# Sheet1.net
KiCad netlist of a schematic drawn in Altium Designer
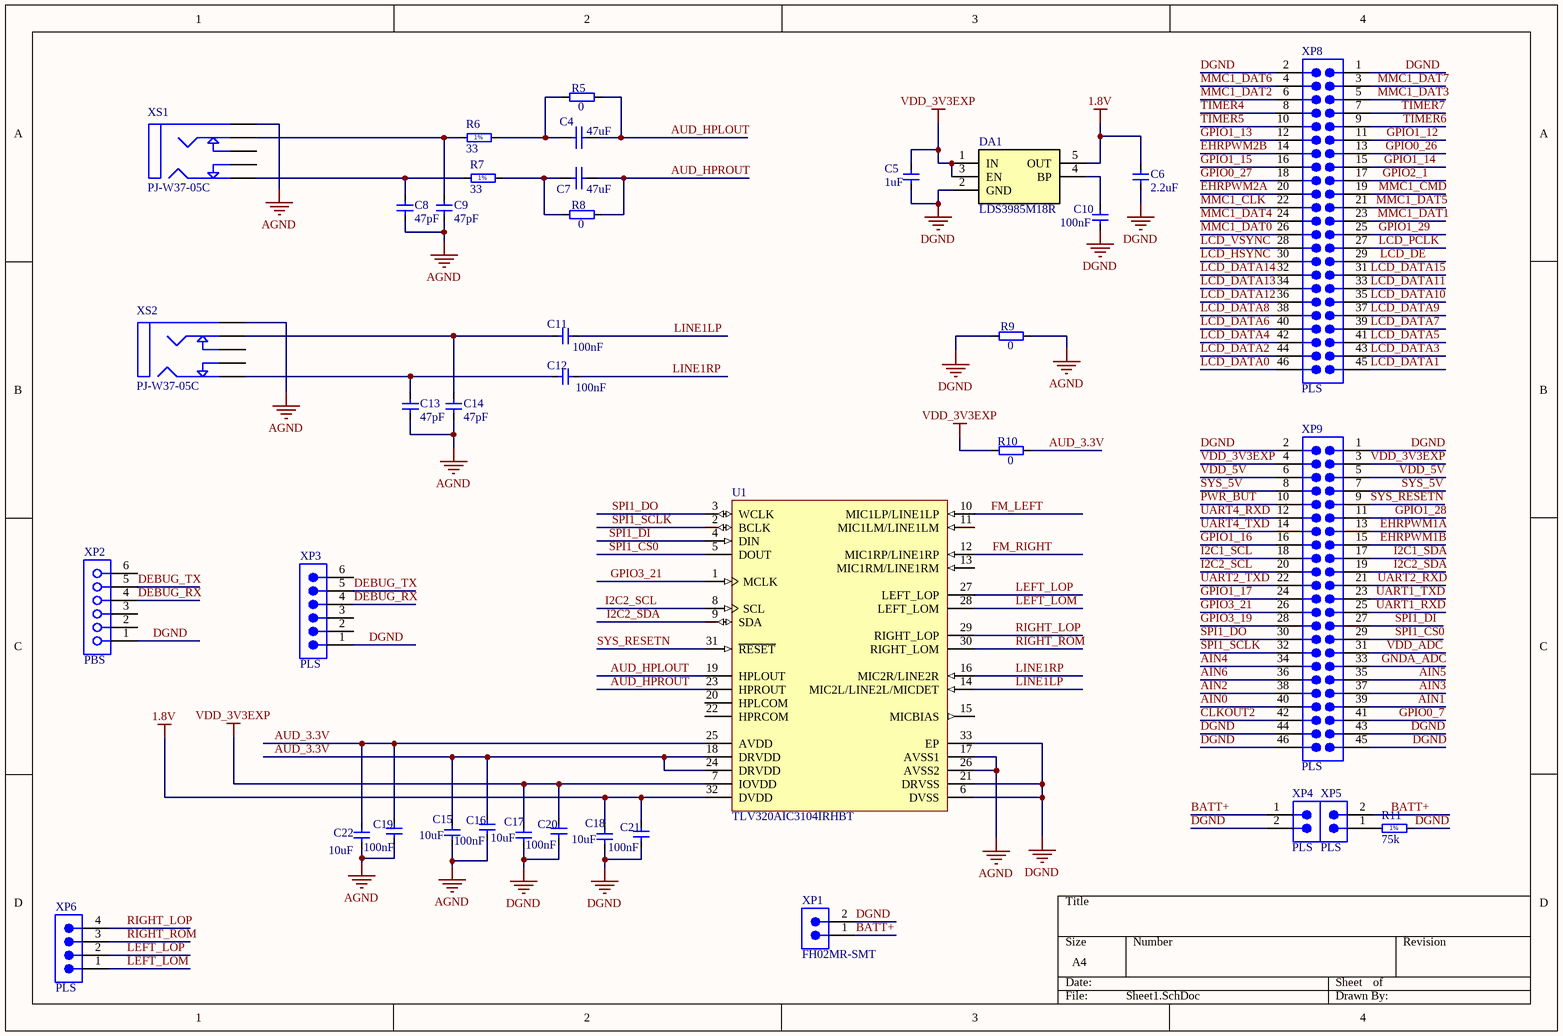
[diagram p0: Sheet1.SchDoc]

(export (version "E")
  (design (tool "Eeschema 10.0.6"))
  (components
    (comp (ref "C4")
      (value "47uF")
      (footprint "CAPC2012X140N")
      (description "Non-polarised capacitor")
      (fields
        (field (name "PART NUMBER") "CC0805_47UF_6.3V_20%_X5R")
        (field (name "VOLTAGE") "6.3V")
        (field (name "AUTHOR") "CERN DEM JLC")
      )
      (libsource (lib "Capacitors") (part "Capacitor - non polarized"))
    )
    (comp (ref "C5")
      (value "1uF")
      (footprint "CAP0603R")
      (description "SMD 0805 Capacitor")
      (fields
        (field (name "PART NUMBER") "CC0603_1UF_16V_10%_X7R")
        (field (name "VOLTAGE") "16V")
        (field (name "AUTHOR") "I. Kuznetsov")
      )
      (libsource (lib "Capacitor") (part "CAP_NON_POLAR"))
    )
    (comp (ref "C6")
      (value "2.2uF")
      (footprint "CAP0603R")
      (description "SMD 0805 Capacitor")
      (fields
        (field (name "PART NUMBER") "CC0603_2.2UF_6.3V_10%_X5R")
        (field (name "VOLTAGE") "6.3V")
        (field (name "AUTHOR") "I. Kuznetsov")
      )
      (libsource (lib "Capacitor") (part "CAP_NON_POLAR"))
    )
    (comp (ref "C7")
      (value "47uF")
      (footprint "CAPC2012X140N")
      (description "Non-polarised capacitor")
      (fields
        (field (name "PART NUMBER") "CC0805_47UF_6.3V_20%_X5R")
        (field (name "VOLTAGE") "6.3V")
        (field (name "AUTHOR") "CERN DEM JLC")
      )
      (libsource (lib "Capacitors") (part "Capacitor - non polarized"))
    )
    (comp (ref "C8")
      (value "47pF")
      (footprint "CAP0603R")
      (description "SMD 0805 Capacitor")
      (fields
        (field (name "PART NUMBER") "CC0603_47PF_50V_5%_NP0")
        (field (name "VOLTAGE") "50V")
        (field (name "AUTHOR") "I. Kuznetsov")
      )
      (libsource (lib "Capacitor") (part "CAP_NON_POLAR"))
    )
    (comp (ref "C9")
      (value "47pF")
      (footprint "CAP0603R")
      (description "SMD 0805 Capacitor")
      (fields
        (field (name "PART NUMBER") "CC0603_47PF_50V_5%_NP0")
        (field (name "VOLTAGE") "50V")
        (field (name "AUTHOR") "I. Kuznetsov")
      )
      (libsource (lib "Capacitor") (part "CAP_NON_POLAR"))
    )
    (comp (ref "C10")
      (value "100nF")
      (footprint "CAP0603R")
      (description "SMD 0805 Capacitor")
      (fields
        (field (name "PART NUMBER") "CC0603_100NF_50V_10%_X7R")
        (field (name "VOLTAGE") "50V")
        (field (name "AUTHOR") "I. Kuznetsov")
      )
      (libsource (lib "Capacitor") (part "CAP_NON_POLAR"))
    )
    (comp (ref "C11")
      (value "100nF")
      (footprint "CAP0603R")
      (description "SMD 0805 Capacitor")
      (fields
        (field (name "PART NUMBER") "CC0603_100NF_50V_10%_X7R")
        (field (name "VOLTAGE") "50V")
        (field (name "AUTHOR") "I. Kuznetsov")
      )
      (libsource (lib "Capacitor") (part "CAP_NON_POLAR"))
    )
    (comp (ref "C12")
      (value "100nF")
      (footprint "CAP0603R")
      (description "SMD 0805 Capacitor")
      (fields
        (field (name "PART NUMBER") "CC0603_100NF_50V_10%_X7R")
        (field (name "VOLTAGE") "50V")
        (field (name "AUTHOR") "I. Kuznetsov")
      )
      (libsource (lib "Capacitor") (part "CAP_NON_POLAR"))
    )
    (comp (ref "C13")
      (value "47pF")
      (footprint "CAP0603R")
      (description "SMD 0805 Capacitor")
      (fields
        (field (name "PART NUMBER") "CC0603_47PF_50V_5%_NP0")
        (field (name "VOLTAGE") "50V")
        (field (name "AUTHOR") "I. Kuznetsov")
      )
      (libsource (lib "Capacitor") (part "CAP_NON_POLAR"))
    )
    (comp (ref "C14")
      (value "47pF")
      (footprint "CAP0603R")
      (description "SMD 0805 Capacitor")
      (fields
        (field (name "PART NUMBER") "CC0603_47PF_50V_5%_NP0")
        (field (name "VOLTAGE") "50V")
        (field (name "AUTHOR") "I. Kuznetsov")
      )
      (libsource (lib "Capacitor") (part "CAP_NON_POLAR"))
    )
    (comp (ref "C15")
      (value "10uF")
      (footprint "CAP0603R")
      (description "SMD 0805 Capacitor")
      (fields
        (field (name "PART NUMBER") "CC0603_10UF_6.3V_20%_X5R")
        (field (name "VOLTAGE") "6.3V")
        (field (name "AUTHOR") "I. Kuznetsov")
      )
      (libsource (lib "Capacitor") (part "CAP_NON_POLAR"))
    )
    (comp (ref "C16")
      (value "100nF")
      (footprint "CAP0603R")
      (description "SMD 0805 Capacitor")
      (fields
        (field (name "PART NUMBER") "CC0603_100NF_50V_10%_X7R")
        (field (name "VOLTAGE") "50V")
        (field (name "AUTHOR") "I. Kuznetsov")
      )
      (libsource (lib "Capacitor") (part "CAP_NON_POLAR"))
    )
    (comp (ref "C17")
      (value "10uF")
      (footprint "CAP0603R")
      (description "SMD 0805 Capacitor")
      (fields
        (field (name "PART NUMBER") "CC0603_10UF_6.3V_20%_X5R")
        (field (name "VOLTAGE") "6.3V")
        (field (name "AUTHOR") "I. Kuznetsov")
      )
      (libsource (lib "Capacitor") (part "CAP_NON_POLAR"))
    )
    (comp (ref "C18")
      (value "10uF")
      (footprint "CAP0603R")
      (description "SMD 0805 Capacitor")
      (fields
        (field (name "PART NUMBER") "CC0603_10UF_6.3V_20%_X5R")
        (field (name "VOLTAGE") "6.3V")
        (field (name "AUTHOR") "I. Kuznetsov")
      )
      (libsource (lib "Capacitor") (part "CAP_NON_POLAR"))
    )
    (comp (ref "C19")
      (value "100nF")
      (footprint "CAP0603R")
      (description "SMD 0805 Capacitor")
      (fields
        (field (name "PART NUMBER") "CC0603_100NF_50V_10%_X7R")
        (field (name "VOLTAGE") "50V")
        (field (name "AUTHOR") "I. Kuznetsov")
      )
      (libsource (lib "Capacitor") (part "CAP_NON_POLAR"))
    )
    (comp (ref "C20")
      (value "100nF")
      (footprint "CAP0603R")
      (description "SMD 0805 Capacitor")
      (fields
        (field (name "PART NUMBER") "CC0603_100NF_50V_10%_X7R")
        (field (name "VOLTAGE") "50V")
        (field (name "AUTHOR") "I. Kuznetsov")
      )
      (libsource (lib "Capacitor") (part "CAP_NON_POLAR"))
    )
    (comp (ref "C21")
      (value "100nF")
      (footprint "CAP0603R")
      (description "SMD 0805 Capacitor")
      (fields
        (field (name "PART NUMBER") "CC0603_100NF_50V_10%_X7R")
        (field (name "VOLTAGE") "50V")
        (field (name "AUTHOR") "I. Kuznetsov")
      )
      (libsource (lib "Capacitor") (part "CAP_NON_POLAR"))
    )
    (comp (ref "C22")
      (value "10uF")
      (footprint "CAP0603R")
      (description "SMD 0805 Capacitor")
      (fields
        (field (name "PART NUMBER") "CC0603_10UF_6.3V_20%_X5R")
        (field (name "VOLTAGE") "6.3V")
        (field (name "AUTHOR") "I. Kuznetsov")
      )
      (libsource (lib "Capacitor") (part "CAP_NON_POLAR"))
    )
    (comp (ref "DA1")
      (value "LDS3985M18R")
      (footprint "SOT23-5")
      (fields (field (name "MANUFACTURER") "ST") (field (name "AUTHOR") "I. Kuznetsov"))
      (libsource (lib "IC And Semiconductor") (part "REG_5_PIN"))
    )
    (comp (ref "R5")
      (value "0")
      (footprint "RESC1608X55N")
      (description "Resistor")
      (fields
        (field (name "PART NUMBER") "R0603_0R_JUMPER")
        (field (name "MANUFACTURER") "GENERIC")
        (field (name "AUTHOR") "CERN DEM JLC")
      )
      (libsource (lib "Resistors") (part "Resistor"))
    )
    (comp (ref "R6")
      (value "33")
      (footprint "RES0603R")
      (fields
        (field (name "PART NUMBER") "R0603_33R_1%_0.1W_100PPM")
        (field (name "POWER") "0.1W")
        (field (name "TOLERANCE") "±1%")
        (field (name "AUTHOR") "CERN DEM JLC")
      )
      (libsource (lib "Resistor") (part "Resistor - 1%"))
    )
    (comp (ref "R7")
      (value "33")
      (footprint "RES0603R")
      (fields
        (field (name "PART NUMBER") "R0603_33R_1%_0.1W_100PPM")
        (field (name "POWER") "0.1W")
        (field (name "TOLERANCE") "±1%")
        (field (name "AUTHOR") "CERN DEM JLC")
      )
      (libsource (lib "Resistor") (part "Resistor - 1%"))
    )
    (comp (ref "R8")
      (value "0")
      (footprint "RESC1608X55N")
      (description "Resistor")
      (fields
        (field (name "PART NUMBER") "R0603_0R_JUMPER")
        (field (name "MANUFACTURER") "GENERIC")
        (field (name "AUTHOR") "CERN DEM JLC")
      )
      (libsource (lib "Resistors") (part "Resistor"))
    )
    (comp (ref "R9")
      (value "0")
      (footprint "RESC1608X55N")
      (description "Resistor")
      (fields
        (field (name "PART NUMBER") "R0603_0R_JUMPER")
        (field (name "MANUFACTURER") "GENERIC")
        (field (name "AUTHOR") "CERN DEM JLC")
      )
      (libsource (lib "Resistors") (part "Resistor"))
    )
    (comp (ref "R10")
      (value "0")
      (footprint "RESC1608X55N")
      (description "Resistor")
      (fields
        (field (name "PART NUMBER") "R0603_0R_JUMPER")
        (field (name "MANUFACTURER") "GENERIC")
        (field (name "AUTHOR") "CERN DEM JLC")
      )
      (libsource (lib "Resistors") (part "Resistor"))
    )
    (comp (ref "R11")
      (value "75k")
      (footprint "RES0603R")
      (fields
        (field (name "PART NUMBER") "R0603_75K_1%_0.1W_100PPM")
        (field (name "POWER") "0.1W")
        (field (name "TOLERANCE") "±1%")
        (field (name "AUTHOR") "CERN DEM JLC")
      )
      (libsource (lib "Resistor") (part "Resistor - 1%"))
    )
    (comp (ref "U1")
      (value "TLV320AIC3104IRHBT")
      (footprint "RHB32-3450X3450TP")
      (fields (field (name "MANUFACTURER") "Texas Instruments"))
      (libsource (lib "Altium Content Vault") (part "TI-TLV320AIC3104RHB32-3450X3450TP"))
    )
    (comp (ref "XP1") (value "FH02MR-SMT") (footprint "FH02MR-SMT") (libsource (lib "") (part "CN_02P_1W_1")))
    (comp (ref "XP2")
      (value "PBS")
      (footprint "PBS-06")
      (fields (field (name "PART NUMBER") "PBS-06"))
      (libsource (lib "Connector") (part "CN_06S_1W"))
    )
    (comp (ref "XP3")
      (value "PLS")
      (footprint "PLS-06")
      (fields (field (name "PART NUMBER") "PLS-06") (field (name "MANUFACTURER") "AUK"))
      (libsource (lib "Connector") (part "CN_06P_1W"))
    )
    (comp (ref "XP4")
      (value "PLS")
      (footprint "PLS-02")
      (fields (field (name "PART NUMBER") "PLS-02") (field (name "MANUFACTURER") "AUK"))
      (libsource (lib "Connector") (part "CN_02P_1W"))
    )
    (comp (ref "XP5")
      (value "PLS")
      (footprint "PLS-02")
      (fields (field (name "PART NUMBER") "PLS-02") (field (name "MANUFACTURER") "AUK"))
      (libsource (lib "") (part "CN_02P_1W_1"))
    )
    (comp (ref "XP6")
      (value "PLS")
      (footprint "PLS-04")
      (fields (field (name "PART NUMBER") "PLS-04") (field (name "MANUFACTURER") "AUK"))
      (libsource (lib "Connector") (part "CN_04P_1W"))
    )
    (comp (ref "XP8")
      (value "PLS")
      (footprint "PLD-46")
      (fields
        (field (name "PART NUMBER") "PLD-46")
        (field (name "MANUFACTURER") "AUK")
        (field (name "MANUFACTURER PART NUMBER") "PLS-16")
      )
      (libsource (lib "Connector") (part "CN_46P_2W"))
    )
    (comp (ref "XP9")
      (value "PLS")
      (footprint "PLD-46")
      (fields
        (field (name "PART NUMBER") "PLD-46")
        (field (name "MANUFACTURER") "AUK")
        (field (name "MANUFACTURER PART NUMBER") "PLS-16")
      )
      (libsource (lib "Connector") (part "CN_46P_2W"))
    )
    (comp (ref "XS1")
      (value "PJ-W37-05C")
      (footprint "PJ-W37-05C")
      (description "3.5 mm Jack Connector")
      (libsource (lib "Connector") (part "SOC_3.5_5_PIN"))
    )
    (comp (ref "XS2")
      (value "PJ-W37-05C")
      (footprint "PJ-W37-05C")
      (description "3.5 mm Jack Connector")
      (libsource (lib "Connector") (part "SOC_3.5_5_PIN"))
    )
  )
  (nets
    (net (code "1") (name "/AIN0") (class "Default")
      (node (ref "XP9") (pin "40") (pinfunction "40_40") (pintype "passive"))
    )
    (net (code "2") (name "/AIN1") (class "Default")
      (node (ref "XP9") (pin "39") (pinfunction "39_39") (pintype "passive"))
    )
    (net (code "3") (name "/AIN2") (class "Default")
      (node (ref "XP9") (pin "38") (pinfunction "38_38") (pintype "passive"))
    )
    (net (code "4") (name "/AIN3") (class "Default")
      (node (ref "XP9") (pin "37") (pinfunction "37_37") (pintype "passive"))
    )
    (net (code "5") (name "/AIN4") (class "Default")
      (node (ref "XP9") (pin "34") (pinfunction "34_34") (pintype "passive"))
    )
    (net (code "6") (name "/AIN5") (class "Default")
      (node (ref "XP9") (pin "35") (pinfunction "35_35") (pintype "passive"))
    )
    (net (code "7") (name "/AIN6") (class "Default")
      (node (ref "XP9") (pin "36") (pinfunction "36_36") (pintype "passive"))
    )
    (net (code "8") (name "/AUD_3.3V") (class "Default")
      (node (ref "C15") (pin "2") (pinfunction "2_2") (pintype "passive"))
      (node (ref "C16") (pin "1") (pinfunction "1_1") (pintype "passive"))
      (node (ref "C19") (pin "1") (pinfunction "1_1") (pintype "passive"))
      (node (ref "C22") (pin "2") (pinfunction "2_2") (pintype "passive"))
      (node (ref "R10") (pin "2") (pinfunction "2_2") (pintype "passive"))
      (node (ref "U1") (pin "18") (pinfunction "DRVDD_18") (pintype "power_in"))
      (node (ref "U1") (pin "24") (pinfunction "DRVDD_24") (pintype "power_in"))
      (node (ref "U1") (pin "25") (pinfunction "AVDD_25") (pintype "power_in"))
    )
    (net (code "9") (name "/AUD_HPLOUT") (class "Default")
      (node (ref "C4") (pin "2") (pinfunction "2_2") (pintype "passive"))
      (node (ref "R5") (pin "2") (pinfunction "2_2") (pintype "passive"))
      (node (ref "U1") (pin "19") (pinfunction "HPLOUT_19") (pintype "tri_state"))
    )
    (net (code "10") (name "/AUD_HPROUT") (class "Default")
      (node (ref "C7") (pin "2") (pinfunction "2_2") (pintype "passive"))
      (node (ref "R8") (pin "2") (pinfunction "2_2") (pintype "passive"))
      (node (ref "U1") (pin "23") (pinfunction "HPROUT_23") (pintype "tri_state"))
    )
    (net (code "11") (name "/BATT+") (class "Default")
      (node (ref "XP1") (pin "1") (pinfunction "1_1") (pintype "passive"))
      (node (ref "XP4") (pin "1") (pinfunction "1_1") (pintype "passive"))
      (node (ref "XP5") (pin "2") (pinfunction "2_2") (pintype "passive"))
    )
    (net (code "12") (name "/CLKOUT2") (class "Default")
      (node (ref "XP9") (pin "42") (pinfunction "42_42") (pintype "passive"))
    )
    (net (code "13") (name "/DEBUG_RX") (class "Default")
      (node (ref "XP2") (pin "4") (pinfunction "4_4") (pintype "passive"))
      (node (ref "XP3") (pin "4") (pinfunction "4_4") (pintype "passive"))
    )
    (net (code "14") (name "/DEBUG_TX") (class "Default")
      (node (ref "XP2") (pin "5") (pinfunction "5_5") (pintype "passive"))
      (node (ref "XP3") (pin "5") (pinfunction "5_5") (pintype "passive"))
    )
    (net (code "15") (name "/EHRPWM1A") (class "Default")
      (node (ref "XP9") (pin "13") (pinfunction "13_13") (pintype "passive"))
    )
    (net (code "16") (name "/EHRPWM1B") (class "Default")
      (node (ref "XP9") (pin "15") (pinfunction "15_15") (pintype "passive"))
    )
    (net (code "17") (name "/EHRPWM2A") (class "Default")
      (node (ref "XP8") (pin "20") (pinfunction "20_20") (pintype "passive"))
    )
    (net (code "18") (name "/EHRPWM2B") (class "Default")
      (node (ref "XP8") (pin "14") (pinfunction "14_14") (pintype "passive"))
    )
    (net (code "19") (name "/FM_LEFT") (class "Default")
      (node (ref "U1") (pin "10") (pinfunction "MIC1LP/LINE1LP_10") (pintype "input"))
    )
    (net (code "20") (name "/FM_RIGHT") (class "Default")
      (node (ref "U1") (pin "12") (pinfunction "MIC1RP/LINE1RP_12") (pintype "input"))
    )
    (net (code "21") (name "/GNDA_ADC") (class "Default")
      (node (ref "XP9") (pin "33") (pinfunction "33_33") (pintype "passive"))
    )
    (net (code "22") (name "/GPIO0_7") (class "Default")
      (node (ref "XP9") (pin "41") (pinfunction "41_41") (pintype "passive"))
    )
    (net (code "23") (name "/GPIO0_26") (class "Default")
      (node (ref "XP8") (pin "13") (pinfunction "13_13") (pintype "passive"))
    )
    (net (code "24") (name "/GPIO0_27") (class "Default")
      (node (ref "XP8") (pin "18") (pinfunction "18_18") (pintype "passive"))
    )
    (net (code "25") (name "/GPIO1_12") (class "Default")
      (node (ref "XP8") (pin "11") (pinfunction "11_11") (pintype "passive"))
    )
    (net (code "26") (name "/GPIO1_13") (class "Default")
      (node (ref "XP8") (pin "12") (pinfunction "12_12") (pintype "passive"))
    )
    (net (code "27") (name "/GPIO1_14") (class "Default")
      (node (ref "XP8") (pin "15") (pinfunction "15_15") (pintype "passive"))
    )
    (net (code "28") (name "/GPIO1_15") (class "Default")
      (node (ref "XP8") (pin "16") (pinfunction "16_16") (pintype "passive"))
    )
    (net (code "29") (name "/GPIO1_16") (class "Default")
      (node (ref "XP9") (pin "16") (pinfunction "16_16") (pintype "passive"))
    )
    (net (code "30") (name "/GPIO1_17") (class "Default")
      (node (ref "XP9") (pin "24") (pinfunction "24_24") (pintype "passive"))
    )
    (net (code "31") (name "/GPIO1_28") (class "Default")
      (node (ref "XP9") (pin "11") (pinfunction "11_11") (pintype "passive"))
    )
    (net (code "32") (name "/GPIO1_29") (class "Default")
      (node (ref "XP8") (pin "25") (pinfunction "25_25") (pintype "passive"))
    )
    (net (code "33") (name "/GPIO2_1") (class "Default")
      (node (ref "XP8") (pin "17") (pinfunction "17_17") (pintype "passive"))
    )
    (net (code "34") (name "/GPIO3_19") (class "Default")
      (node (ref "XP9") (pin "28") (pinfunction "28_28") (pintype "passive"))
    )
    (net (code "35") (name "/GPIO3_21") (class "Default")
      (node (ref "U1") (pin "1") (pinfunction "MCLK_1") (pintype "input"))
      (node (ref "XP9") (pin "26") (pinfunction "26_26") (pintype "passive"))
    )
    (net (code "36") (name "/I2C1_SCL") (class "Default")
      (node (ref "XP9") (pin "18") (pinfunction "18_18") (pintype "passive"))
    )
    (net (code "37") (name "/I2C1_SDA") (class "Default")
      (node (ref "XP9") (pin "17") (pinfunction "17_17") (pintype "passive"))
    )
    (net (code "38") (name "/I2C2_SCL") (class "Default")
      (node (ref "U1") (pin "8") (pinfunction "SCL_8") (pintype "input"))
      (node (ref "XP9") (pin "20") (pinfunction "20_20") (pintype "passive"))
    )
    (net (code "39") (name "/I2C2_SDA") (class "Default")
      (node (ref "U1") (pin "9") (pinfunction "SDA_9") (pintype "bidirectional"))
      (node (ref "XP9") (pin "19") (pinfunction "19_19") (pintype "passive"))
    )
    (net (code "40") (name "/LCD_DATA0") (class "Default")
      (node (ref "XP8") (pin "46") (pinfunction "46_46") (pintype "passive"))
    )
    (net (code "41") (name "/LCD_DATA1") (class "Default")
      (node (ref "XP8") (pin "45") (pinfunction "45_45") (pintype "passive"))
    )
    (net (code "42") (name "/LCD_DATA2") (class "Default")
      (node (ref "XP8") (pin "44") (pinfunction "44_44") (pintype "passive"))
    )
    (net (code "43") (name "/LCD_DATA3") (class "Default")
      (node (ref "XP8") (pin "43") (pinfunction "43_43") (pintype "passive"))
    )
    (net (code "44") (name "/LCD_DATA4") (class "Default")
      (node (ref "XP8") (pin "42") (pinfunction "42_42") (pintype "passive"))
    )
    (net (code "45") (name "/LCD_DATA5") (class "Default")
      (node (ref "XP8") (pin "41") (pinfunction "41_41") (pintype "passive"))
    )
    (net (code "46") (name "/LCD_DATA6") (class "Default")
      (node (ref "XP8") (pin "40") (pinfunction "40_40") (pintype "passive"))
    )
    (net (code "47") (name "/LCD_DATA7") (class "Default")
      (node (ref "XP8") (pin "39") (pinfunction "39_39") (pintype "passive"))
    )
    (net (code "48") (name "/LCD_DATA8") (class "Default")
      (node (ref "XP8") (pin "38") (pinfunction "38_38") (pintype "passive"))
    )
    (net (code "49") (name "/LCD_DATA9") (class "Default")
      (node (ref "XP8") (pin "37") (pinfunction "37_37") (pintype "passive"))
    )
    (net (code "50") (name "/LCD_DATA10") (class "Default")
      (node (ref "XP8") (pin "35") (pinfunction "35_35") (pintype "passive"))
    )
    (net (code "51") (name "/LCD_DATA11") (class "Default")
      (node (ref "XP8") (pin "33") (pinfunction "33_33") (pintype "passive"))
    )
    (net (code "52") (name "/LCD_DATA12") (class "Default")
      (node (ref "XP8") (pin "36") (pinfunction "36_36") (pintype "passive"))
    )
    (net (code "53") (name "/LCD_DATA13") (class "Default")
      (node (ref "XP8") (pin "34") (pinfunction "34_34") (pintype "passive"))
    )
    (net (code "54") (name "/LCD_DATA14") (class "Default")
      (node (ref "XP8") (pin "32") (pinfunction "32_32") (pintype "passive"))
    )
    (net (code "55") (name "/LCD_DATA15") (class "Default")
      (node (ref "XP8") (pin "31") (pinfunction "31_31") (pintype "passive"))
    )
    (net (code "56") (name "/LCD_DE") (class "Default")
      (node (ref "XP8") (pin "29") (pinfunction "29_29") (pintype "passive"))
    )
    (net (code "57") (name "/LCD_HSYNC") (class "Default")
      (node (ref "XP8") (pin "30") (pinfunction "30_30") (pintype "passive"))
    )
    (net (code "58") (name "/LCD_PCLK") (class "Default")
      (node (ref "XP8") (pin "27") (pinfunction "27_27") (pintype "passive"))
    )
    (net (code "59") (name "/LCD_VSYNC") (class "Default")
      (node (ref "XP8") (pin "28") (pinfunction "28_28") (pintype "passive"))
    )
    (net (code "60") (name "/LEFT_LOM") (class "Default")
      (node (ref "U1") (pin "28") (pinfunction "LEFT_LOM_28") (pintype "tri_state"))
      (node (ref "XP6") (pin "1") (pinfunction "1_1") (pintype "passive"))
    )
    (net (code "61") (name "/LEFT_LOP") (class "Default")
      (node (ref "U1") (pin "27") (pinfunction "LEFT_LOP_27") (pintype "tri_state"))
      (node (ref "XP6") (pin "2") (pinfunction "2_2") (pintype "passive"))
    )
    (net (code "62") (name "/LINE1LP") (class "Default")
      (node (ref "C11") (pin "2") (pinfunction "2_2") (pintype "passive"))
      (node (ref "U1") (pin "14") (pinfunction "MIC2L/LINE2L/MICDET_14") (pintype "input"))
    )
    (net (code "63") (name "/LINE1RP") (class "Default")
      (node (ref "C12") (pin "2") (pinfunction "2_2") (pintype "passive"))
      (node (ref "U1") (pin "16") (pinfunction "MIC2R/LINE2R_16") (pintype "input"))
    )
    (net (code "64") (name "/MMC1_CLK") (class "Default")
      (node (ref "XP8") (pin "22") (pinfunction "22_22") (pintype "passive"))
    )
    (net (code "65") (name "/MMC1_CMD") (class "Default")
      (node (ref "XP8") (pin "19") (pinfunction "19_19") (pintype "passive"))
    )
    (net (code "66") (name "/MMC1_DAT0") (class "Default")
      (node (ref "XP8") (pin "26") (pinfunction "26_26") (pintype "passive"))
    )
    (net (code "67") (name "/MMC1_DAT1") (class "Default")
      (node (ref "XP8") (pin "23") (pinfunction "23_23") (pintype "passive"))
    )
    (net (code "68") (name "/MMC1_DAT2") (class "Default")
      (node (ref "XP8") (pin "6") (pinfunction "6_6") (pintype "passive"))
    )
    (net (code "69") (name "/MMC1_DAT3") (class "Default")
      (node (ref "XP8") (pin "5") (pinfunction "5_5") (pintype "passive"))
    )
    (net (code "70") (name "/MMC1_DAT4") (class "Default")
      (node (ref "XP8") (pin "24") (pinfunction "24_24") (pintype "passive"))
    )
    (net (code "71") (name "/MMC1_DAT5") (class "Default")
      (node (ref "XP8") (pin "21") (pinfunction "21_21") (pintype "passive"))
    )
    (net (code "72") (name "/MMC1_DAT6") (class "Default")
      (node (ref "XP8") (pin "4") (pinfunction "4_4") (pintype "passive"))
    )
    (net (code "73") (name "/MMC1_DAT7") (class "Default")
      (node (ref "XP8") (pin "3") (pinfunction "3_3") (pintype "passive"))
    )
    (net (code "74") (name "/PWR_BUT") (class "Default")
      (node (ref "XP9") (pin "10") (pinfunction "10_10") (pintype "passive"))
    )
    (net (code "75") (name "/RIGHT_LOP") (class "Default")
      (node (ref "U1") (pin "29") (pinfunction "RIGHT_LOP_29") (pintype "tri_state"))
      (node (ref "XP6") (pin "4") (pinfunction "4_4") (pintype "passive"))
    )
    (net (code "76") (name "/RIGHT_ROM") (class "Default")
      (node (ref "U1") (pin "30") (pinfunction "RIGHT_LOM_30") (pintype "tri_state"))
      (node (ref "XP6") (pin "3") (pinfunction "3_3") (pintype "passive"))
    )
    (net (code "77") (name "/SPI1_CS0") (class "Default")
      (node (ref "U1") (pin "5") (pinfunction "DOUT_5") (pintype "tri_state"))
      (node (ref "XP9") (pin "29") (pinfunction "29_29") (pintype "passive"))
    )
    (net (code "78") (name "/SPI1_DI") (class "Default")
      (node (ref "U1") (pin "4") (pinfunction "DIN_4") (pintype "input"))
      (node (ref "XP9") (pin "27") (pinfunction "27_27") (pintype "passive"))
    )
    (net (code "79") (name "/SPI1_DO") (class "Default")
      (node (ref "U1") (pin "3") (pinfunction "WCLK_3") (pintype "bidirectional"))
      (node (ref "XP9") (pin "30") (pinfunction "30_30") (pintype "passive"))
    )
    (net (code "80") (name "/SPI1_SCLK") (class "Default")
      (node (ref "U1") (pin "2") (pinfunction "BCLK_2") (pintype "bidirectional"))
      (node (ref "XP9") (pin "32") (pinfunction "32_32") (pintype "passive"))
    )
    (net (code "81") (name "/SYS_5V") (class "Default")
      (node (ref "XP9") (pin "7") (pinfunction "7_7") (pintype "passive"))
      (node (ref "XP9") (pin "8") (pinfunction "8_8") (pintype "passive"))
    )
    (net (code "82") (name "/SYS_RESETN") (class "Default")
      (node (ref "U1") (pin "31") (pinfunction "~{RESET}_31") (pintype "input"))
      (node (ref "XP9") (pin "9") (pinfunction "9_9") (pintype "passive"))
    )
    (net (code "83") (name "/TIMER4") (class "Default")
      (node (ref "XP8") (pin "8") (pinfunction "8_8") (pintype "passive"))
    )
    (net (code "84") (name "/TIMER5") (class "Default")
      (node (ref "XP8") (pin "10") (pinfunction "10_10") (pintype "passive"))
    )
    (net (code "85") (name "/TIMER6") (class "Default")
      (node (ref "XP8") (pin "9") (pinfunction "9_9") (pintype "passive"))
    )
    (net (code "86") (name "/TIMER7") (class "Default")
      (node (ref "XP8") (pin "7") (pinfunction "7_7") (pintype "passive"))
    )
    (net (code "87") (name "/UART1_RXD") (class "Default")
      (node (ref "XP9") (pin "25") (pinfunction "25_25") (pintype "passive"))
    )
    (net (code "88") (name "/UART1_TXD") (class "Default")
      (node (ref "XP9") (pin "23") (pinfunction "23_23") (pintype "passive"))
    )
    (net (code "89") (name "/UART2_RXD") (class "Default")
      (node (ref "XP9") (pin "21") (pinfunction "21_21") (pintype "passive"))
    )
    (net (code "90") (name "/UART2_TXD") (class "Default")
      (node (ref "XP9") (pin "22") (pinfunction "22_22") (pintype "passive"))
    )
    (net (code "91") (name "/UART4_RXD") (class "Default")
      (node (ref "XP9") (pin "12") (pinfunction "12_12") (pintype "passive"))
    )
    (net (code "92") (name "/UART4_TXD") (class "Default")
      (node (ref "XP9") (pin "14") (pinfunction "14_14") (pintype "passive"))
    )
    (net (code "93") (name "/VDD_5V") (class "Default")
      (node (ref "XP9") (pin "5") (pinfunction "5_5") (pintype "passive"))
      (node (ref "XP9") (pin "6") (pinfunction "6_6") (pintype "passive"))
    )
    (net (code "94") (name "/VDD_ADC") (class "Default")
      (node (ref "XP9") (pin "31") (pinfunction "31_31") (pintype "passive"))
    )
    (net (code "95") (name "1.8V") (class "Default")
      (node (ref "C18") (pin "2") (pinfunction "2_2") (pintype "passive"))
      (node (ref "C21") (pin "1") (pinfunction "1_1") (pintype "passive"))
      (node (ref "C6") (pin "2") (pinfunction "2_2") (pintype "passive"))
      (node (ref "DA1") (pin "5") (pinfunction "OUT_5") (pintype "passive"))
      (node (ref "U1") (pin "32") (pinfunction "DVDD_32") (pintype "power_in"))
    )
    (net (code "96") (name "AGND") (class "Default")
      (node (ref "C13") (pin "2") (pinfunction "2_2") (pintype "passive"))
      (node (ref "C14") (pin "2") (pinfunction "2_2") (pintype "passive"))
      (node (ref "C15") (pin "1") (pinfunction "1_1") (pintype "passive"))
      (node (ref "C16") (pin "2") (pinfunction "2_2") (pintype "passive"))
      (node (ref "C19") (pin "2") (pinfunction "2_2") (pintype "passive"))
      (node (ref "C22") (pin "1") (pinfunction "1_1") (pintype "passive"))
      (node (ref "C8") (pin "2") (pinfunction "2_2") (pintype "passive"))
      (node (ref "C9") (pin "2") (pinfunction "2_2") (pintype "passive"))
      (node (ref "R9") (pin "2") (pinfunction "2_2") (pintype "passive"))
      (node (ref "U1") (pin "17") (pinfunction "AVSS1_17") (pintype "power_in"))
      (node (ref "U1") (pin "26") (pinfunction "AVSS2_26") (pintype "power_in"))
      (node (ref "XS1") (pin "1") (pinfunction "1_1") (pintype "passive"))
      (node (ref "XS2") (pin "1") (pinfunction "1_1") (pintype "passive"))
    )
    (net (code "97") (name "DGND") (class "Default")
      (node (ref "C10") (pin "1") (pinfunction "1_1") (pintype "passive"))
      (node (ref "C17") (pin "1") (pinfunction "1_1") (pintype "passive"))
      (node (ref "C18") (pin "1") (pinfunction "1_1") (pintype "passive"))
      (node (ref "C20") (pin "2") (pinfunction "2_2") (pintype "passive"))
      (node (ref "C21") (pin "2") (pinfunction "2_2") (pintype "passive"))
      (node (ref "C5") (pin "2") (pinfunction "2_2") (pintype "passive"))
      (node (ref "C6") (pin "1") (pinfunction "1_1") (pintype "passive"))
      (node (ref "DA1") (pin "2") (pinfunction "GND_2") (pintype "passive"))
      (node (ref "R11") (pin "2") (pinfunction "2_2") (pintype "passive"))
      (node (ref "R9") (pin "1") (pinfunction "1_1") (pintype "passive"))
      (node (ref "U1") (pin "21") (pinfunction "DRVSS_21") (pintype "power_in"))
      (node (ref "U1") (pin "33") (pinfunction "EP_33") (pintype "power_in"))
      (node (ref "U1") (pin "6") (pinfunction "DVSS_6") (pintype "power_in"))
      (node (ref "XP1") (pin "2") (pinfunction "2_2") (pintype "passive"))
      (node (ref "XP2") (pin "1") (pinfunction "1_1") (pintype "passive"))
      (node (ref "XP3") (pin "1") (pinfunction "1_1") (pintype "passive"))
      (node (ref "XP4") (pin "2") (pinfunction "2_2") (pintype "passive"))
      (node (ref "XP8") (pin "1") (pinfunction "1_1") (pintype "passive"))
      (node (ref "XP8") (pin "2") (pinfunction "2_2") (pintype "passive"))
      (node (ref "XP9") (pin "1") (pinfunction "1_1") (pintype "passive"))
      (node (ref "XP9") (pin "2") (pinfunction "2_2") (pintype "passive"))
      (node (ref "XP9") (pin "43") (pinfunction "43_43") (pintype "passive"))
      (node (ref "XP9") (pin "44") (pinfunction "44_44") (pintype "passive"))
      (node (ref "XP9") (pin "45") (pinfunction "45_45") (pintype "passive"))
      (node (ref "XP9") (pin "46") (pinfunction "46_46") (pintype "passive"))
    )
    (net (code "98") (name "Net-(C4-Pad1)") (class "Default")
      (node (ref "C4") (pin "1") (pinfunction "1_1") (pintype "passive"))
      (node (ref "R5") (pin "1") (pinfunction "1_1") (pintype "passive"))
      (node (ref "R6") (pin "2") (pinfunction "2_2") (pintype "passive"))
    )
    (net (code "99") (name "Net-(C7-Pad1)") (class "Default")
      (node (ref "C7") (pin "1") (pinfunction "1_1") (pintype "passive"))
      (node (ref "R7") (pin "2") (pinfunction "2_2") (pintype "passive"))
      (node (ref "R8") (pin "1") (pinfunction "1_1") (pintype "passive"))
    )
    (net (code "100") (name "Net-(C8-Pad1)") (class "Default")
      (node (ref "C8") (pin "1") (pinfunction "1_1") (pintype "passive"))
      (node (ref "R7") (pin "1") (pinfunction "1_1") (pintype "passive"))
      (node (ref "XS1") (pin "3") (pinfunction "3_3") (pintype "passive"))
    )
    (net (code "101") (name "Net-(C9-Pad1)") (class "Default")
      (node (ref "C9") (pin "1") (pinfunction "1_1") (pintype "passive"))
      (node (ref "R6") (pin "1") (pinfunction "1_1") (pintype "passive"))
      (node (ref "XS1") (pin "2") (pinfunction "2_2") (pintype "passive"))
    )
    (net (code "102") (name "Net-(C11-Pad1)") (class "Default")
      (node (ref "C11") (pin "1") (pinfunction "1_1") (pintype "passive"))
      (node (ref "C14") (pin "1") (pinfunction "1_1") (pintype "passive"))
      (node (ref "XS2") (pin "2") (pinfunction "2_2") (pintype "passive"))
    )
    (net (code "103") (name "Net-(C12-Pad1)") (class "Default")
      (node (ref "C12") (pin "1") (pinfunction "1_1") (pintype "passive"))
      (node (ref "C13") (pin "1") (pinfunction "1_1") (pintype "passive"))
      (node (ref "XS2") (pin "3") (pinfunction "3_3") (pintype "passive"))
    )
    (net (code "104") (name "Net-(DA1-BP)") (class "Default")
      (node (ref "C10") (pin "2") (pinfunction "2_2") (pintype "passive"))
      (node (ref "DA1") (pin "4") (pinfunction "BP_4") (pintype "passive"))
    )
    (net (code "105") (name "Net-(R11-Pad1)") (class "Default")
      (node (ref "R11") (pin "1") (pinfunction "1_1") (pintype "passive"))
      (node (ref "XP5") (pin "1") (pinfunction "1_1") (pintype "passive"))
    )
    (net (code "106") (name "VDD_3V3EXP") (class "Default")
      (node (ref "C17") (pin "2") (pinfunction "2_2") (pintype "passive"))
      (node (ref "C20") (pin "1") (pinfunction "1_1") (pintype "passive"))
      (node (ref "C5") (pin "1") (pinfunction "1_1") (pintype "passive"))
      (node (ref "DA1") (pin "1") (pinfunction "IN_1") (pintype "passive"))
      (node (ref "DA1") (pin "3") (pinfunction "EN_3") (pintype "passive"))
      (node (ref "R10") (pin "1") (pinfunction "1_1") (pintype "passive"))
      (node (ref "U1") (pin "7") (pinfunction "IOVDD_7") (pintype "power_in"))
      (node (ref "XP9") (pin "3") (pinfunction "3_3") (pintype "passive"))
      (node (ref "XP9") (pin "4") (pinfunction "4_4") (pintype "passive"))
    )
    (net (code "107") (name "unconnected-(U1-HPLCOM-Pad20)") (class "Default")
      (node (ref "U1") (pin "20") (pinfunction "HPLCOM_20") (pintype "tri_state"))
    )
    (net (code "108") (name "unconnected-(U1-HPRCOM-Pad22)") (class "Default")
      (node (ref "U1") (pin "22") (pinfunction "HPRCOM_22") (pintype "tri_state"))
    )
    (net (code "109") (name "unconnected-(U1-MIC1LM{slash}LINE1LM-Pad11)") (class "Default")
      (node (ref "U1") (pin "11") (pinfunction "MIC1LM/LINE1LM_11") (pintype "input"))
    )
    (net (code "110") (name "unconnected-(U1-MIC1RM{slash}LINE1RM-Pad13)") (class "Default")
      (node (ref "U1") (pin "13") (pinfunction "MIC1RM/LINE1RM_13") (pintype "input"))
    )
    (net (code "111") (name "unconnected-(U1-MICBIAS-Pad15)") (class "Default")
      (node (ref "U1") (pin "15") (pinfunction "MICBIAS_15") (pintype "output"))
    )
    (net (code "112") (name "unconnected-(XP2-Pad2)") (class "Default")
      (node (ref "XP2") (pin "2") (pinfunction "2_2") (pintype "passive"))
    )
    (net (code "113") (name "unconnected-(XP2-Pad3)") (class "Default")
      (node (ref "XP2") (pin "3") (pinfunction "3_3") (pintype "passive"))
    )
    (net (code "114") (name "unconnected-(XP2-Pad6)") (class "Default")
      (node (ref "XP2") (pin "6") (pinfunction "6_6") (pintype "passive"))
    )
    (net (code "115") (name "unconnected-(XP3-Pad2)") (class "Default")
      (node (ref "XP3") (pin "2") (pinfunction "2_2") (pintype "passive"))
    )
    (net (code "116") (name "unconnected-(XP3-Pad3)") (class "Default")
      (node (ref "XP3") (pin "3") (pinfunction "3_3") (pintype "passive"))
    )
    (net (code "117") (name "unconnected-(XP3-Pad6)") (class "Default")
      (node (ref "XP3") (pin "6") (pinfunction "6_6") (pintype "passive"))
    )
    (net (code "118") (name "unconnected-(XS1-Pad4)") (class "Default")
      (node (ref "XS1") (pin "4") (pinfunction "4_4") (pintype "passive"))
    )
    (net (code "119") (name "unconnected-(XS1-Pad5)") (class "Default")
      (node (ref "XS1") (pin "5") (pinfunction "5_5") (pintype "passive"))
    )
    (net (code "120") (name "unconnected-(XS2-Pad4)") (class "Default")
      (node (ref "XS2") (pin "4") (pinfunction "4_4") (pintype "passive"))
    )
    (net (code "121") (name "unconnected-(XS2-Pad5)") (class "Default")
      (node (ref "XS2") (pin "5") (pinfunction "5_5") (pintype "passive"))
    )
  )
)
